# YOTSUBA_-Y-Z_ver_1_2.net
KiCad netlist of a schematic drawn in EAGLE
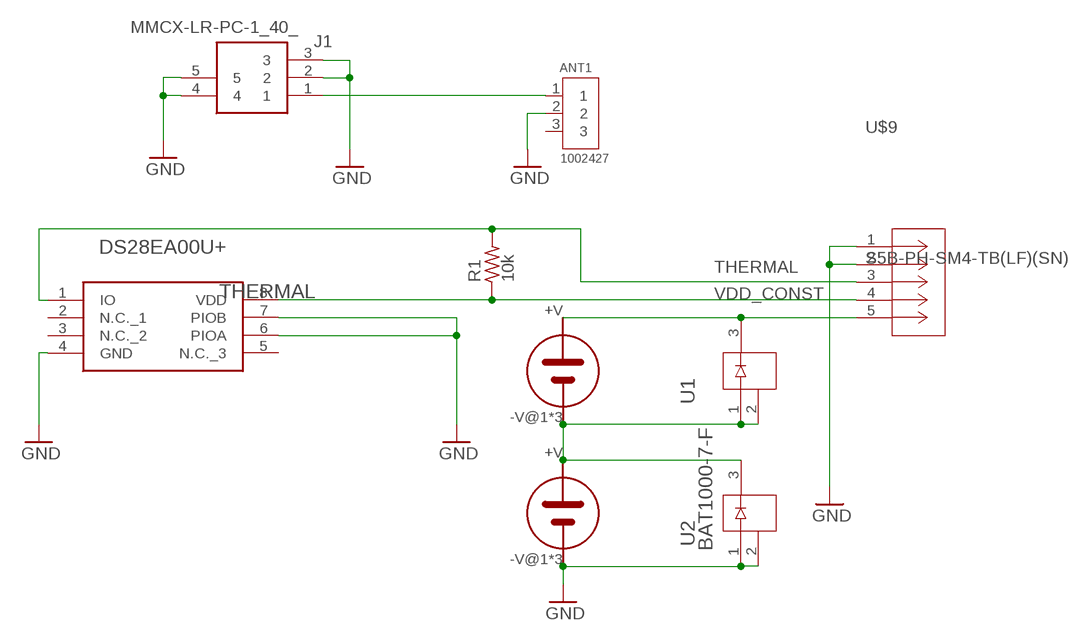
[diagram p0: schematic, sheet 1]

(export (version "E")
  (design (tool "Eeschema 10.0.6"))
  (components
    (comp (ref "ANT1")
      (value "1002427")
      (footprint "eagle-import:ANTENNA_1002427")
      (fields (field (name "DIGI-KEY_PART_NUMBER") "478-1002427TR-ND") (field (name "MF") "Ethertronics/AVX"))
      (libsource (lib "eagle-import") (part "1002427"))
    )
    (comp (ref "J1")
      (value "MMCX-LR-PC-1_40_")
      (footprint "eagle-import:MMCXLRPC140")
      (fields
        (field (name "MANUFACTURER_PART_NUMBER") "MMCX-LR-PC-1(40)")
        (field (name "MOUSER_PART_NUMBER") "798-MMCX-LR-PC-1(40)")
      )
      (libsource (lib "eagle-import") (part "MMCX-LR-PC-1_40_"))
    )
    (comp (ref "R1")
      (value "10k")
      (footprint "eagle-import:R0805")
      (libsource (lib "eagle-import") (part "R-US_R0805"))
    )
    (comp (ref "THERMAL")
      (value "DS28EA00U+")
      (footprint "eagle-import:SOP65P490X110-8N")
      (fields (field (name "MOUSER_PART_NUMBER") "700-DS28EA00U"))
      (libsource (lib "eagle-import") (part "DS28EA00U+"))
    )
    (comp (ref "U$2")
      (value "3G30A")
      (footprint "eagle-import:SOLAR_3G30A")
      (libsource (lib "eagle-import") (part "3G30A"))
    )
    (comp (ref "U$3")
      (value "3G30A")
      (footprint "eagle-import:SOLAR_3G30A")
      (libsource (lib "eagle-import") (part "3G30A"))
    )
    (comp (ref "U$9")
      (value "S5B-PH-SM4-TB(LF)(SN)")
      (footprint "eagle-import:CONN_S5B-PH-SM4-TB_JST")
      (fields (field (name "COPYRIGHT") "Copyright (C) 2023 Ultra Librarian. All rights reserved."))
      (libsource (lib "eagle-import") (part "S5B-PH-SM4-TB(LF)(SN)"))
    )
    (comp (ref "U1")
      (value "BAT1000-7-F")
      (footprint "eagle-import:SOT23_BAT_DIO")
      (fields (field (name "COPYRIGHT") "Copyright (C) 2023 Ultra Librarian. All rights reserved."))
      (libsource (lib "eagle-import") (part "BAT1000-7-F"))
    )
    (comp (ref "U2")
      (value "BAT1000-7-F")
      (footprint "eagle-import:SOT23_BAT_DIO")
      (fields (field (name "COPYRIGHT") "Copyright (C) 2023 Ultra Librarian. All rights reserved."))
      (libsource (lib "eagle-import") (part "BAT1000-7-F"))
    )
  )
  (nets
    (net (code "1") (name "/THERMAL") (class "Default")
      (node (ref "R1") (pin "2") (pinfunction "2_2") (pintype "passive"))
      (node (ref "THERMAL") (pin "1") (pinfunction "IO_1") (pintype "bidirectional"))
      (node (ref "U$9") (pin "3") (pinfunction "3_3") (pintype "passive"))
    )
    (net (code "2") (name "/VDD_CONST") (class "Default")
      (node (ref "R1") (pin "1") (pinfunction "1_1") (pintype "passive"))
      (node (ref "THERMAL") (pin "8") (pinfunction "VDD_8") (pintype "bidirectional"))
      (node (ref "U$9") (pin "4") (pinfunction "4_4") (pintype "passive"))
    )
    (net (code "3") (name "GND") (class "Default")
      (node (ref "ANT1") (pin "2") (pinfunction "2_2") (pintype "passive"))
      (node (ref "J1") (pin "2") (pinfunction "2_2") (pintype "bidirectional"))
      (node (ref "J1") (pin "3") (pinfunction "3_3") (pintype "bidirectional"))
      (node (ref "J1") (pin "4") (pinfunction "4_4") (pintype "bidirectional"))
      (node (ref "J1") (pin "5") (pinfunction "5_5") (pintype "bidirectional"))
      (node (ref "THERMAL") (pin "4") (pinfunction "GND_4") (pintype "bidirectional"))
      (node (ref "THERMAL") (pin "6") (pinfunction "PIOA_6") (pintype "bidirectional"))
      (node (ref "THERMAL") (pin "7") (pinfunction "PIOB_7") (pintype "bidirectional"))
      (node (ref "U$3") (pin "-V@1") (pinfunction "-V_-V@1") (pintype "bidirectional"))
      (node (ref "U$3") (pin "-V@2") (pinfunction "-V_-V@2") (pintype "bidirectional"))
      (node (ref "U$3") (pin "-V@3") (pinfunction "-V_-V@3") (pintype "bidirectional"))
      (node (ref "U$9") (pin "1") (pinfunction "1_1") (pintype "passive"))
      (node (ref "U$9") (pin "2") (pinfunction "2_2") (pintype "passive"))
      (node (ref "U2") (pin "1") (pinfunction "1_1") (pintype "passive"))
      (node (ref "U2") (pin "2") (pinfunction "2_2") (pintype "passive"))
    )
    (net (code "4") (name "Net-(ANT1-Pad1)") (class "Default")
      (node (ref "ANT1") (pin "1") (pinfunction "1_1") (pintype "passive"))
      (node (ref "J1") (pin "1") (pinfunction "1_1") (pintype "bidirectional"))
    )
    (net (code "5") (name "Net-(U$2--V-Pad-V@1)") (class "Default")
      (node (ref "U$2") (pin "-V@1") (pinfunction "-V_-V@1") (pintype "bidirectional"))
      (node (ref "U$2") (pin "-V@2") (pinfunction "-V_-V@2") (pintype "bidirectional"))
      (node (ref "U$2") (pin "-V@3") (pinfunction "-V_-V@3") (pintype "bidirectional"))
      (node (ref "U$3") (pin "+V") (pinfunction "+V_+V") (pintype "bidirectional"))
      (node (ref "U1") (pin "1") (pinfunction "1_1") (pintype "passive"))
      (node (ref "U1") (pin "2") (pinfunction "2_2") (pintype "passive"))
      (node (ref "U2") (pin "3") (pinfunction "3_3") (pintype "passive"))
    )
    (net (code "6") (name "Net-(U$2-Pad+V)") (class "Default")
      (node (ref "U$2") (pin "+V") (pinfunction "+V_+V") (pintype "bidirectional"))
      (node (ref "U$9") (pin "5") (pinfunction "5_5") (pintype "passive"))
      (node (ref "U1") (pin "3") (pinfunction "3_3") (pintype "passive"))
    )
    (net (code "7") (name "unconnected-(ANT1-Pad3)") (class "Default")
      (node (ref "ANT1") (pin "3") (pinfunction "3_3") (pintype "passive"))
    )
    (net (code "8") (name "unconnected-(THERMAL-N.C._1-Pad2)") (class "Default")
      (node (ref "THERMAL") (pin "2") (pinfunction "N.C._1_2") (pintype "bidirectional"))
    )
    (net (code "9") (name "unconnected-(THERMAL-N.C._2-Pad3)") (class "Default")
      (node (ref "THERMAL") (pin "3") (pinfunction "N.C._2_3") (pintype "bidirectional"))
    )
    (net (code "10") (name "unconnected-(THERMAL-N.C._3-Pad5)") (class "Default")
      (node (ref "THERMAL") (pin "5") (pinfunction "N.C._3_5") (pintype "bidirectional"))
    )
  )
)
